# 0_Overview.net
KiCad netlist of a schematic drawn in Altium Designer
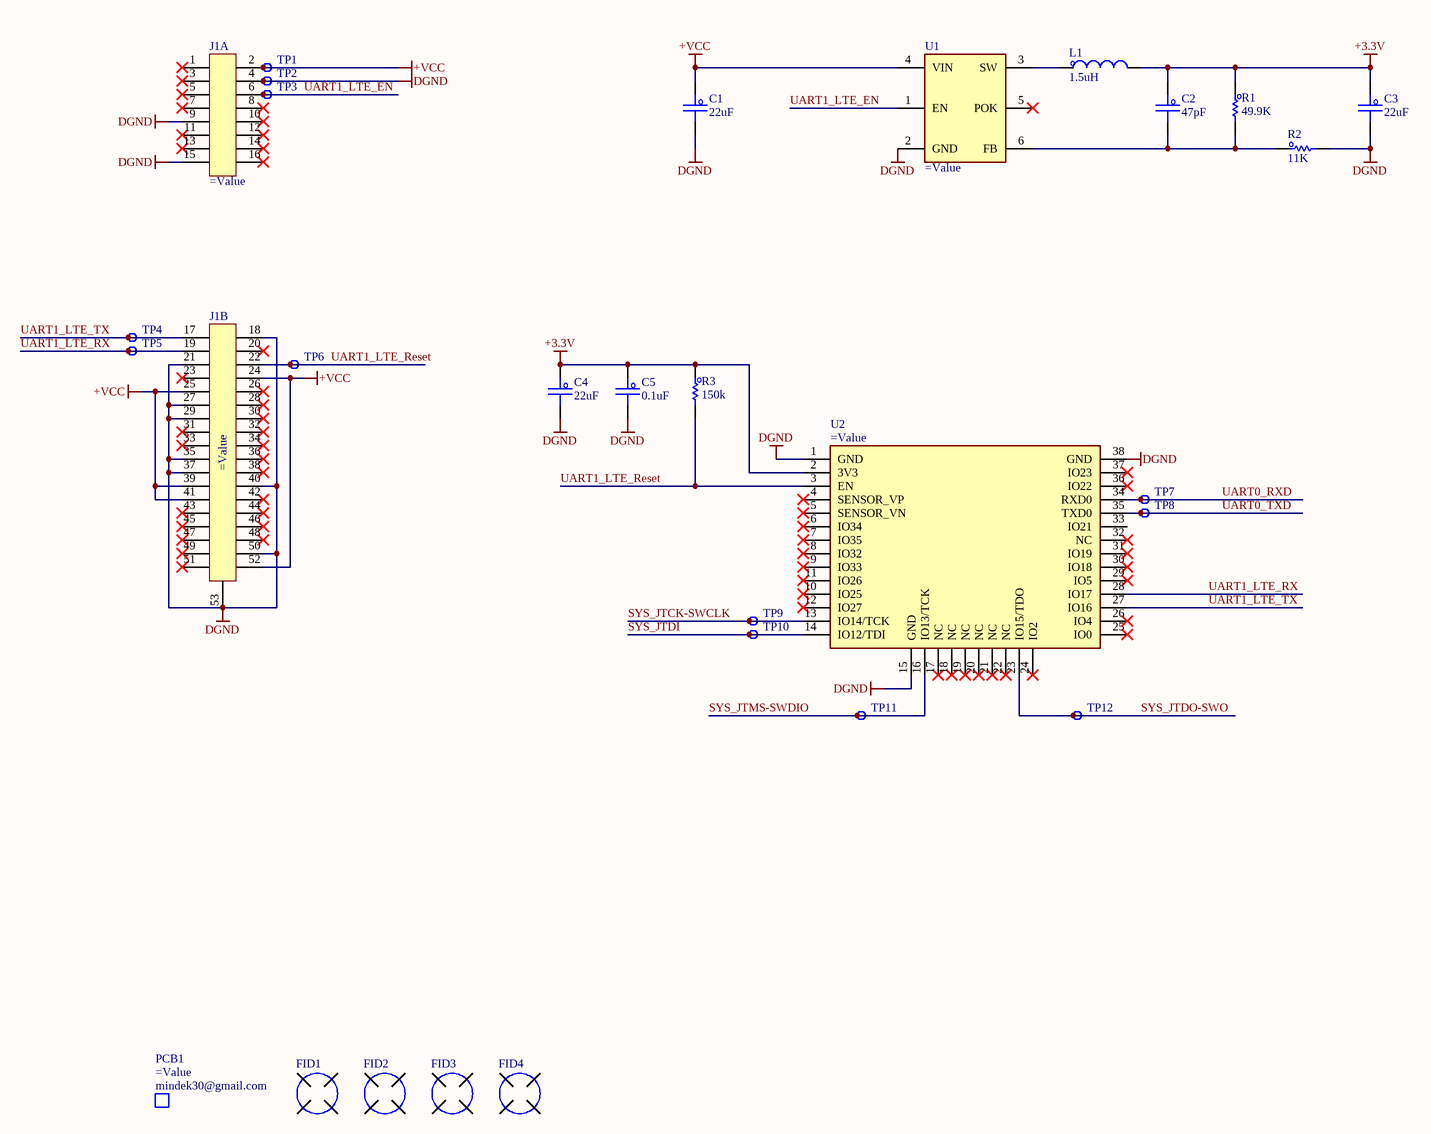
[diagram p0: 0_Overview.SchDoc]

(export (version "E")
  (design (tool "Eeschema 10.0.6"))
  (components
    (comp (ref "C1")
      (value "22uF")
      (footprint "C_0603")
      (description "CAP CER 22UF 10V X5R 0603")
      (fields
        (field (name "MANUFACTURER") "TDK Corporation")
        (field (name "PARTNUMBER") "C1608X5R1A226M080AC")
      )
      (libsource (lib "UUSymbol") (part "C_Capacitor"))
    )
    (comp (ref "C2")
      (value "47pF")
      (footprint "C_0603")
      (description "CAP CER 47PF 50V X7R 0603")
      (fields (field (name "MANUFACTURER") "KEMET") (field (name "PARTNUMBER") "C0603C470J5RAC7867"))
      (libsource (lib "UUSymbol") (part "C_Capacitor"))
    )
    (comp (ref "C3")
      (value "22uF")
      (footprint "C_0603")
      (description "CAP CER 22UF 10V X5R 0603")
      (fields
        (field (name "MANUFACTURER") "TDK Corporation")
        (field (name "PARTNUMBER") "C1608X5R1A226M080AC")
      )
      (libsource (lib "UUSymbol") (part "C_Capacitor"))
    )
    (comp (ref "C4")
      (value "22uF")
      (footprint "C_0603")
      (description "CAP CER 22UF 10V X5R 0603")
      (fields
        (field (name "MANUFACTURER") "TDK Corporation")
        (field (name "PARTNUMBER") "C1608X5R1A226M080AC")
      )
      (libsource (lib "UUSymbol") (part "C_Capacitor"))
    )
    (comp (ref "C5")
      (value "0.1uF")
      (footprint "C_0603")
      (description "CAP CER 0.1UF 50V X7R 0603")
      (fields (field (name "MANUFACTURER") "KEMET") (field (name "PARTNUMBER") "C0603C104K5RACTU"))
      (libsource (lib "UUSymbol") (part "C_Capacitor"))
    )
    (comp (ref "FID1")
      (value "FIDUCIAL")
      (footprint "FID")
      (description "Fiducial")
      (fields (field (name "MANUFACTURER") "mindek30@gmail.com") (field (name "PARTNUMBER") "_"))
      (libsource (lib "UUSymbol") (part "FID_FIDUCIAL"))
    )
    (comp (ref "FID2")
      (value "FIDUCIAL")
      (footprint "FID")
      (description "Fiducial")
      (fields (field (name "MANUFACTURER") "mindek30@gmail.com") (field (name "PARTNUMBER") "_"))
      (libsource (lib "UUSymbol") (part "FID_FIDUCIAL"))
    )
    (comp (ref "FID3")
      (value "FIDUCIAL")
      (footprint "FID")
      (description "Fiducial")
      (fields (field (name "MANUFACTURER") "mindek30@gmail.com") (field (name "PARTNUMBER") "_"))
      (libsource (lib "UUSymbol") (part "FID_FIDUCIAL"))
    )
    (comp (ref "FID4")
      (value "FIDUCIAL")
      (footprint "FID")
      (description "Fiducial")
      (fields (field (name "MANUFACTURER") "mindek30@gmail.com") (field (name "PARTNUMBER") "_"))
      (libsource (lib "UUSymbol") (part "FID_FIDUCIAL"))
    )
    (comp (ref "J1")
      (value "~")
      (footprint "PCIeMini-GF-2D-800-1K-S52")
      (description "CONN PCI EXP MINI FEMALE 52POS")
      (fields
        (field (name "PARTNUMBER") "2041119-1")
        (field (name "MANUFACTURER") "TE Connectivity AMP Connectors")
      )
      (libsource (lib "UUSymbol") (part "CON_PCI-E-52P"))
    )
    (comp (ref "L1")
      (value "1.5uH")
      (footprint "L_0603")
      (description "10µH Shielded Multilayer Inductor 250mA 1.05Ohm 0603 (1608 Metric)")
      (fields (field (name "MANUFACTURER") "Taiyo Yuden") (field (name "PARTNUMBER") "MBKK1608T1R5M"))
      (libsource (lib "UUSymbol") (part "L_Inductor"))
    )
    (comp (ref "PCB1")
      (value "~")
      (description "BARE PCB")
      (fields (field (name "MANUFACTURER") "mindek30@gmail.com") (field (name "PARTNUMBER") "_"))
      (libsource (lib "UUSymbol") (part "PCB_Bare"))
    )
    (comp (ref "R1")
      (value "49.9K")
      (footprint "R_0603")
      (description "RES 120K OHM 5% 1/10W 0603")
      (fields (field (name "MANUFACTURER") "Vishay Dale") (field (name "PARTNUMBER") "CRCW060349K9FKEAC"))
      (libsource (lib "UUSymbol") (part "R_Resister"))
    )
    (comp (ref "R2")
      (value "11K")
      (footprint "R_0603")
      (description "RES 11K OHM 1% 1/10W 0603")
      (fields (field (name "MANUFACTURER") "Vishay Dale") (field (name "PARTNUMBER") "CRCW060311K0FKEAC"))
      (libsource (lib "UUSymbol") (part "R_Resister"))
    )
    (comp (ref "R3")
      (value "150k")
      (footprint "R_0603")
      (description "RES SMD 150K OHM 1% 1/10W 0603")
      (fields (field (name "MANUFACTURER") "Vishay Dale") (field (name "PARTNUMBER") "CRCW0603150KFKEAC"))
      (libsource (lib "UUSymbol") (part "R_Resister"))
    )
    (comp (ref "TP1")
      (value "~")
      (footprint "TP_Testpoint")
      (description "TestPoint")
      (libsource (lib "UUSymbol") (part "TP_TestPoint"))
    )
    (comp (ref "TP2")
      (value "~")
      (footprint "TP_Testpoint")
      (description "TestPoint")
      (libsource (lib "UUSymbol") (part "TP_TestPoint"))
    )
    (comp (ref "TP3")
      (value "~")
      (footprint "TP_Testpoint")
      (description "TestPoint")
      (libsource (lib "UUSymbol") (part "TP_TestPoint"))
    )
    (comp (ref "TP4")
      (value "~")
      (footprint "TP_Testpoint")
      (description "TestPoint")
      (libsource (lib "UUSymbol") (part "TP_TestPoint"))
    )
    (comp (ref "TP5")
      (value "~")
      (footprint "TP_Testpoint")
      (description "TestPoint")
      (libsource (lib "UUSymbol") (part "TP_TestPoint"))
    )
    (comp (ref "TP6")
      (value "~")
      (footprint "TP_Testpoint")
      (description "TestPoint")
      (libsource (lib "UUSymbol") (part "TP_TestPoint"))
    )
    (comp (ref "TP7")
      (value "~")
      (footprint "TP_Testpoint")
      (description "TestPoint")
      (libsource (lib "UUSymbol") (part "TP_TestPoint"))
    )
    (comp (ref "TP8")
      (value "~")
      (footprint "TP_Testpoint")
      (description "TestPoint")
      (libsource (lib "UUSymbol") (part "TP_TestPoint"))
    )
    (comp (ref "TP9")
      (value "~")
      (footprint "TP_Testpoint")
      (description "TestPoint")
      (libsource (lib "UUSymbol") (part "TP_TestPoint"))
    )
    (comp (ref "TP10")
      (value "~")
      (footprint "TP_Testpoint")
      (description "TestPoint")
      (libsource (lib "UUSymbol") (part "TP_TestPoint"))
    )
    (comp (ref "TP11")
      (value "~")
      (footprint "TP_Testpoint")
      (description "TestPoint")
      (libsource (lib "UUSymbol") (part "TP_TestPoint"))
    )
    (comp (ref "TP12")
      (value "~")
      (footprint "TP_Testpoint")
      (description "TestPoint")
      (libsource (lib "UUSymbol") (part "TP_TestPoint"))
    )
    (comp (ref "U1")
      (value "~")
      (footprint "SOT95P270X115-6M")
      (description "DC DC CONVERTER 5V 5W")
      (fields (field (name "PARTNUMBER") "JW5222") (field (name "MANUFACTURER") "JoulWatt Tech"))
      (libsource (lib "UUSymbol") (part "IC_PMS_JW5222"))
    )
    (comp (ref "U2")
      (value "~")
      (footprint "MODULE_ESP32-WROOM-32UE")
      (description "RX TXRX MODULE WIFI U.FL SMD")
      (fields
        (field (name "MANUFACTURER") "Espressif Systems")
        (field (name "PARTNUMBER") "ESP32-WROOM-32UE (8MB)")
      )
      (libsource (lib "UUSymbol") (part "IC_MCU_ESP32-WROOM-32UE"))
    )
  )
  (nets
    (net (code "1") (name "+3.3V") (class "Default")
      (node (ref "C2") (pin "1") (pinfunction "1_1") (pintype "passive"))
      (node (ref "C3") (pin "1") (pinfunction "1_1") (pintype "passive"))
      (node (ref "C4") (pin "1") (pinfunction "1_1") (pintype "passive"))
      (node (ref "C5") (pin "1") (pinfunction "1_1") (pintype "passive"))
      (node (ref "L1") (pin "2") (pinfunction "2_2") (pintype "passive"))
      (node (ref "R1") (pin "1") (pinfunction "1_1") (pintype "passive"))
      (node (ref "R3") (pin "1") (pinfunction "1_1") (pintype "passive"))
      (node (ref "U2") (pin "2") (pinfunction "3V3_2") (pintype "passive"))
    )
    (net (code "2") (name "+VCC") (class "Default")
      (node (ref "C1") (pin "1") (pinfunction "1_1") (pintype "passive"))
      (node (ref "J1") (pin "2") (pinfunction "2_2") (pintype "passive"))
      (node (ref "J1") (pin "24") (pinfunction "24_24") (pintype "passive"))
      (node (ref "J1") (pin "25") (pinfunction "25_25") (pintype "passive"))
      (node (ref "J1") (pin "39") (pinfunction "39_39") (pintype "passive"))
      (node (ref "J1") (pin "41") (pinfunction "41_41") (pintype "passive"))
      (node (ref "J1") (pin "52") (pinfunction "52_52") (pintype "passive"))
      (node (ref "TP1") (pin "1") (pinfunction "1_1") (pintype "passive"))
      (node (ref "U1") (pin "4") (pinfunction "VIN_4") (pintype "passive"))
    )
    (net (code "3") (name "/SYS_JTCK-SWCLK") (class "Default")
      (node (ref "TP9") (pin "1") (pinfunction "1_1") (pintype "passive"))
      (node (ref "U2") (pin "13") (pinfunction "IO14/TCK_13") (pintype "passive"))
    )
    (net (code "4") (name "/SYS_JTDI") (class "Default")
      (node (ref "TP10") (pin "1") (pinfunction "1_1") (pintype "passive"))
      (node (ref "U2") (pin "14") (pinfunction "IO12/TDI_14") (pintype "passive"))
    )
    (net (code "5") (name "/SYS_JTDO-SWO") (class "Default")
      (node (ref "TP12") (pin "1") (pinfunction "1_1") (pintype "passive"))
      (node (ref "U2") (pin "23") (pinfunction "IO15/TDO_23") (pintype "passive"))
    )
    (net (code "6") (name "/SYS_JTMS-SWDIO") (class "Default")
      (node (ref "TP11") (pin "1") (pinfunction "1_1") (pintype "passive"))
      (node (ref "U2") (pin "16") (pinfunction "IO13/TCK_16") (pintype "passive"))
    )
    (net (code "7") (name "/UART0_RXD") (class "Default")
      (node (ref "TP7") (pin "1") (pinfunction "1_1") (pintype "passive"))
      (node (ref "U2") (pin "34") (pinfunction "RXD0_34") (pintype "passive"))
    )
    (net (code "8") (name "/UART0_TXD") (class "Default")
      (node (ref "TP8") (pin "1") (pinfunction "1_1") (pintype "passive"))
      (node (ref "U2") (pin "35") (pinfunction "TXD0_35") (pintype "passive"))
    )
    (net (code "9") (name "/UART1_LTE_EN") (class "Default")
      (node (ref "J1") (pin "6") (pinfunction "6_6") (pintype "passive"))
      (node (ref "TP3") (pin "1") (pinfunction "1_1") (pintype "passive"))
      (node (ref "U1") (pin "1") (pinfunction "EN_1") (pintype "passive"))
    )
    (net (code "10") (name "/UART1_LTE_RX") (class "Default")
      (node (ref "J1") (pin "19") (pinfunction "19_19") (pintype "passive"))
      (node (ref "TP5") (pin "1") (pinfunction "1_1") (pintype "passive"))
      (node (ref "U2") (pin "28") (pinfunction "IO17_28") (pintype "passive"))
    )
    (net (code "11") (name "/UART1_LTE_Reset") (class "Default")
      (node (ref "J1") (pin "22") (pinfunction "22_22") (pintype "passive"))
      (node (ref "R3") (pin "2") (pinfunction "2_2") (pintype "passive"))
      (node (ref "TP6") (pin "1") (pinfunction "1_1") (pintype "passive"))
      (node (ref "U2") (pin "3") (pinfunction "EN_3") (pintype "passive"))
    )
    (net (code "12") (name "/UART1_LTE_TX") (class "Default")
      (node (ref "J1") (pin "17") (pinfunction "17_17") (pintype "passive"))
      (node (ref "TP4") (pin "1") (pinfunction "1_1") (pintype "passive"))
      (node (ref "U2") (pin "27") (pinfunction "IO16_27") (pintype "passive"))
    )
    (net (code "13") (name "DGND") (class "Default")
      (node (ref "C1") (pin "2") (pinfunction "2_2") (pintype "passive"))
      (node (ref "C3") (pin "2") (pinfunction "2_2") (pintype "passive"))
      (node (ref "C4") (pin "2") (pinfunction "2_2") (pintype "passive"))
      (node (ref "C5") (pin "2") (pinfunction "2_2") (pintype "passive"))
      (node (ref "J1") (pin "15") (pinfunction "15_15") (pintype "passive"))
      (node (ref "J1") (pin "18") (pinfunction "18_18") (pintype "passive"))
      (node (ref "J1") (pin "21") (pinfunction "21_21") (pintype "passive"))
      (node (ref "J1") (pin "27") (pinfunction "27_27") (pintype "passive"))
      (node (ref "J1") (pin "29") (pinfunction "29_29") (pintype "passive"))
      (node (ref "J1") (pin "35") (pinfunction "35_35") (pintype "passive"))
      (node (ref "J1") (pin "37") (pinfunction "37_37") (pintype "passive"))
      (node (ref "J1") (pin "4") (pinfunction "4_4") (pintype "passive"))
      (node (ref "J1") (pin "40") (pinfunction "40_40") (pintype "passive"))
      (node (ref "J1") (pin "50") (pinfunction "50_50") (pintype "passive"))
      (node (ref "J1") (pin "53") (pinfunction "53_53") (pintype "passive"))
      (node (ref "J1") (pin "9") (pinfunction "9_9") (pintype "passive"))
      (node (ref "R2") (pin "2") (pinfunction "2_2") (pintype "passive"))
      (node (ref "TP2") (pin "1") (pinfunction "1_1") (pintype "passive"))
      (node (ref "U1") (pin "2") (pinfunction "GND_2") (pintype "passive"))
      (node (ref "U2") (pin "1") (pinfunction "GND_1") (pintype "passive"))
      (node (ref "U2") (pin "15") (pinfunction "GND_15") (pintype "passive"))
      (node (ref "U2") (pin "38") (pinfunction "GND_38") (pintype "passive"))
    )
    (net (code "14") (name "Net-(U1-FB)") (class "Default")
      (node (ref "C2") (pin "2") (pinfunction "2_2") (pintype "passive"))
      (node (ref "R1") (pin "2") (pinfunction "2_2") (pintype "passive"))
      (node (ref "R2") (pin "1") (pinfunction "1_1") (pintype "passive"))
      (node (ref "U1") (pin "6") (pinfunction "FB_6") (pintype "passive"))
    )
    (net (code "15") (name "Net-(U1-SW)") (class "Default")
      (node (ref "L1") (pin "1") (pinfunction "1_1") (pintype "passive"))
      (node (ref "U1") (pin "3") (pinfunction "SW_3") (pintype "passive"))
    )
    (net (code "16") (name "unconnected-(J1-Pad1)") (class "Default")
      (node (ref "J1") (pin "1") (pinfunction "1_1") (pintype "passive+no_connect"))
    )
    (net (code "17") (name "unconnected-(J1-Pad3)") (class "Default")
      (node (ref "J1") (pin "3") (pinfunction "3_3") (pintype "passive+no_connect"))
    )
    (net (code "18") (name "unconnected-(J1-Pad5)") (class "Default")
      (node (ref "J1") (pin "5") (pinfunction "5_5") (pintype "passive+no_connect"))
    )
    (net (code "19") (name "unconnected-(J1-Pad7)") (class "Default")
      (node (ref "J1") (pin "7") (pinfunction "7_7") (pintype "passive+no_connect"))
    )
    (net (code "20") (name "unconnected-(J1-Pad8)") (class "Default")
      (node (ref "J1") (pin "8") (pinfunction "8_8") (pintype "passive+no_connect"))
    )
    (net (code "21") (name "unconnected-(J1-Pad10)") (class "Default")
      (node (ref "J1") (pin "10") (pinfunction "10_10") (pintype "passive+no_connect"))
    )
    (net (code "22") (name "unconnected-(J1-Pad11)") (class "Default")
      (node (ref "J1") (pin "11") (pinfunction "11_11") (pintype "passive+no_connect"))
    )
    (net (code "23") (name "unconnected-(J1-Pad12)") (class "Default")
      (node (ref "J1") (pin "12") (pinfunction "12_12") (pintype "passive+no_connect"))
    )
    (net (code "24") (name "unconnected-(J1-Pad13)") (class "Default")
      (node (ref "J1") (pin "13") (pinfunction "13_13") (pintype "passive+no_connect"))
    )
    (net (code "25") (name "unconnected-(J1-Pad14)") (class "Default")
      (node (ref "J1") (pin "14") (pinfunction "14_14") (pintype "passive+no_connect"))
    )
    (net (code "26") (name "unconnected-(J1-Pad16)") (class "Default")
      (node (ref "J1") (pin "16") (pinfunction "16_16") (pintype "passive+no_connect"))
    )
    (net (code "27") (name "unconnected-(J1-Pad20)") (class "Default")
      (node (ref "J1") (pin "20") (pinfunction "20_20") (pintype "passive+no_connect"))
    )
    (net (code "28") (name "unconnected-(J1-Pad23)") (class "Default")
      (node (ref "J1") (pin "23") (pinfunction "23_23") (pintype "passive+no_connect"))
    )
    (net (code "29") (name "unconnected-(J1-Pad26)") (class "Default")
      (node (ref "J1") (pin "26") (pinfunction "26_26") (pintype "passive+no_connect"))
    )
    (net (code "30") (name "unconnected-(J1-Pad28)") (class "Default")
      (node (ref "J1") (pin "28") (pinfunction "28_28") (pintype "passive+no_connect"))
    )
    (net (code "31") (name "unconnected-(J1-Pad30)") (class "Default")
      (node (ref "J1") (pin "30") (pinfunction "30_30") (pintype "passive+no_connect"))
    )
    (net (code "32") (name "unconnected-(J1-Pad31)") (class "Default")
      (node (ref "J1") (pin "31") (pinfunction "31_31") (pintype "passive+no_connect"))
    )
    (net (code "33") (name "unconnected-(J1-Pad32)") (class "Default")
      (node (ref "J1") (pin "32") (pinfunction "32_32") (pintype "passive+no_connect"))
    )
    (net (code "34") (name "unconnected-(J1-Pad33)") (class "Default")
      (node (ref "J1") (pin "33") (pinfunction "33_33") (pintype "passive+no_connect"))
    )
    (net (code "35") (name "unconnected-(J1-Pad34)") (class "Default")
      (node (ref "J1") (pin "34") (pinfunction "34_34") (pintype "passive+no_connect"))
    )
    (net (code "36") (name "unconnected-(J1-Pad36)") (class "Default")
      (node (ref "J1") (pin "36") (pinfunction "36_36") (pintype "passive+no_connect"))
    )
    (net (code "37") (name "unconnected-(J1-Pad38)") (class "Default")
      (node (ref "J1") (pin "38") (pinfunction "38_38") (pintype "passive+no_connect"))
    )
    (net (code "38") (name "unconnected-(J1-Pad42)") (class "Default")
      (node (ref "J1") (pin "42") (pinfunction "42_42") (pintype "passive+no_connect"))
    )
    (net (code "39") (name "unconnected-(J1-Pad43)") (class "Default")
      (node (ref "J1") (pin "43") (pinfunction "43_43") (pintype "passive+no_connect"))
    )
    (net (code "40") (name "unconnected-(J1-Pad44)") (class "Default")
      (node (ref "J1") (pin "44") (pinfunction "44_44") (pintype "passive+no_connect"))
    )
    (net (code "41") (name "unconnected-(J1-Pad45)") (class "Default")
      (node (ref "J1") (pin "45") (pinfunction "45_45") (pintype "passive+no_connect"))
    )
    (net (code "42") (name "unconnected-(J1-Pad46)") (class "Default")
      (node (ref "J1") (pin "46") (pinfunction "46_46") (pintype "passive+no_connect"))
    )
    (net (code "43") (name "unconnected-(J1-Pad47)") (class "Default")
      (node (ref "J1") (pin "47") (pinfunction "47_47") (pintype "passive+no_connect"))
    )
    (net (code "44") (name "unconnected-(J1-Pad48)") (class "Default")
      (node (ref "J1") (pin "48") (pinfunction "48_48") (pintype "passive+no_connect"))
    )
    (net (code "45") (name "unconnected-(J1-Pad49)") (class "Default")
      (node (ref "J1") (pin "49") (pinfunction "49_49") (pintype "passive+no_connect"))
    )
    (net (code "46") (name "unconnected-(J1-Pad51)") (class "Default")
      (node (ref "J1") (pin "51") (pinfunction "51_51") (pintype "passive+no_connect"))
    )
    (net (code "47") (name "unconnected-(U1-POK-Pad5)") (class "Default")
      (node (ref "U1") (pin "5") (pinfunction "POK_5") (pintype "passive+no_connect"))
    )
    (net (code "48") (name "unconnected-(U2-IO0-Pad25)") (class "Default")
      (node (ref "U2") (pin "25") (pinfunction "IO0_25") (pintype "passive+no_connect"))
    )
    (net (code "49") (name "unconnected-(U2-IO2-Pad24)") (class "Default")
      (node (ref "U2") (pin "24") (pinfunction "IO2_24") (pintype "passive+no_connect"))
    )
    (net (code "50") (name "unconnected-(U2-IO4-Pad26)") (class "Default")
      (node (ref "U2") (pin "26") (pinfunction "IO4_26") (pintype "passive+no_connect"))
    )
    (net (code "51") (name "unconnected-(U2-IO5-Pad29)") (class "Default")
      (node (ref "U2") (pin "29") (pinfunction "IO5_29") (pintype "passive+no_connect"))
    )
    (net (code "52") (name "unconnected-(U2-IO18-Pad30)") (class "Default")
      (node (ref "U2") (pin "30") (pinfunction "IO18_30") (pintype "passive+no_connect"))
    )
    (net (code "53") (name "unconnected-(U2-IO19-Pad31)") (class "Default")
      (node (ref "U2") (pin "31") (pinfunction "IO19_31") (pintype "passive+no_connect"))
    )
    (net (code "54") (name "unconnected-(U2-IO21-Pad33)") (class "Default")
      (node (ref "U2") (pin "33") (pinfunction "IO21_33") (pintype "passive"))
    )
    (net (code "55") (name "unconnected-(U2-IO22-Pad36)") (class "Default")
      (node (ref "U2") (pin "36") (pinfunction "IO22_36") (pintype "passive+no_connect"))
    )
    (net (code "56") (name "unconnected-(U2-IO23-Pad37)") (class "Default")
      (node (ref "U2") (pin "37") (pinfunction "IO23_37") (pintype "passive+no_connect"))
    )
    (net (code "57") (name "unconnected-(U2-IO25-Pad10)") (class "Default")
      (node (ref "U2") (pin "10") (pinfunction "IO25_10") (pintype "passive+no_connect"))
    )
    (net (code "58") (name "unconnected-(U2-IO26-Pad11)") (class "Default")
      (node (ref "U2") (pin "11") (pinfunction "IO26_11") (pintype "passive+no_connect"))
    )
    (net (code "59") (name "unconnected-(U2-IO27-Pad12)") (class "Default")
      (node (ref "U2") (pin "12") (pinfunction "IO27_12") (pintype "passive+no_connect"))
    )
    (net (code "60") (name "unconnected-(U2-IO32-Pad8)") (class "Default")
      (node (ref "U2") (pin "8") (pinfunction "IO32_8") (pintype "passive+no_connect"))
    )
    (net (code "61") (name "unconnected-(U2-IO33-Pad9)") (class "Default")
      (node (ref "U2") (pin "9") (pinfunction "IO33_9") (pintype "passive+no_connect"))
    )
    (net (code "62") (name "unconnected-(U2-IO34-Pad6)") (class "Default")
      (node (ref "U2") (pin "6") (pinfunction "IO34_6") (pintype "passive+no_connect"))
    )
    (net (code "63") (name "unconnected-(U2-IO35-Pad7)") (class "Default")
      (node (ref "U2") (pin "7") (pinfunction "IO35_7") (pintype "passive+no_connect"))
    )
    (net (code "64") (name "unconnected-(U2-NC-Pad17)") (class "Default")
      (node (ref "U2") (pin "17") (pinfunction "NC_17") (pintype "passive+no_connect"))
    )
    (net (code "65") (name "unconnected-(U2-NC-Pad18)") (class "Default")
      (node (ref "U2") (pin "18") (pinfunction "NC_18") (pintype "passive+no_connect"))
    )
    (net (code "66") (name "unconnected-(U2-NC-Pad19)") (class "Default")
      (node (ref "U2") (pin "19") (pinfunction "NC_19") (pintype "passive+no_connect"))
    )
    (net (code "67") (name "unconnected-(U2-NC-Pad20)") (class "Default")
      (node (ref "U2") (pin "20") (pinfunction "NC_20") (pintype "passive+no_connect"))
    )
    (net (code "68") (name "unconnected-(U2-NC-Pad21)") (class "Default")
      (node (ref "U2") (pin "21") (pinfunction "NC_21") (pintype "passive+no_connect"))
    )
    (net (code "69") (name "unconnected-(U2-NC-Pad22)") (class "Default")
      (node (ref "U2") (pin "22") (pinfunction "NC_22") (pintype "passive+no_connect"))
    )
    (net (code "70") (name "unconnected-(U2-NC-Pad32)") (class "Default")
      (node (ref "U2") (pin "32") (pinfunction "NC_32") (pintype "passive+no_connect"))
    )
    (net (code "71") (name "unconnected-(U2-SENSOR_VN-Pad5)") (class "Default")
      (node (ref "U2") (pin "5") (pinfunction "SENSOR_VN_5") (pintype "passive+no_connect"))
    )
    (net (code "72") (name "unconnected-(U2-SENSOR_VP-Pad4)") (class "Default")
      (node (ref "U2") (pin "4") (pinfunction "SENSOR_VP_4") (pintype "passive+no_connect"))
    )
  )
)
